# Interface_Load_Switching.net
KiCad netlist of a schematic drawn in Altium Designer
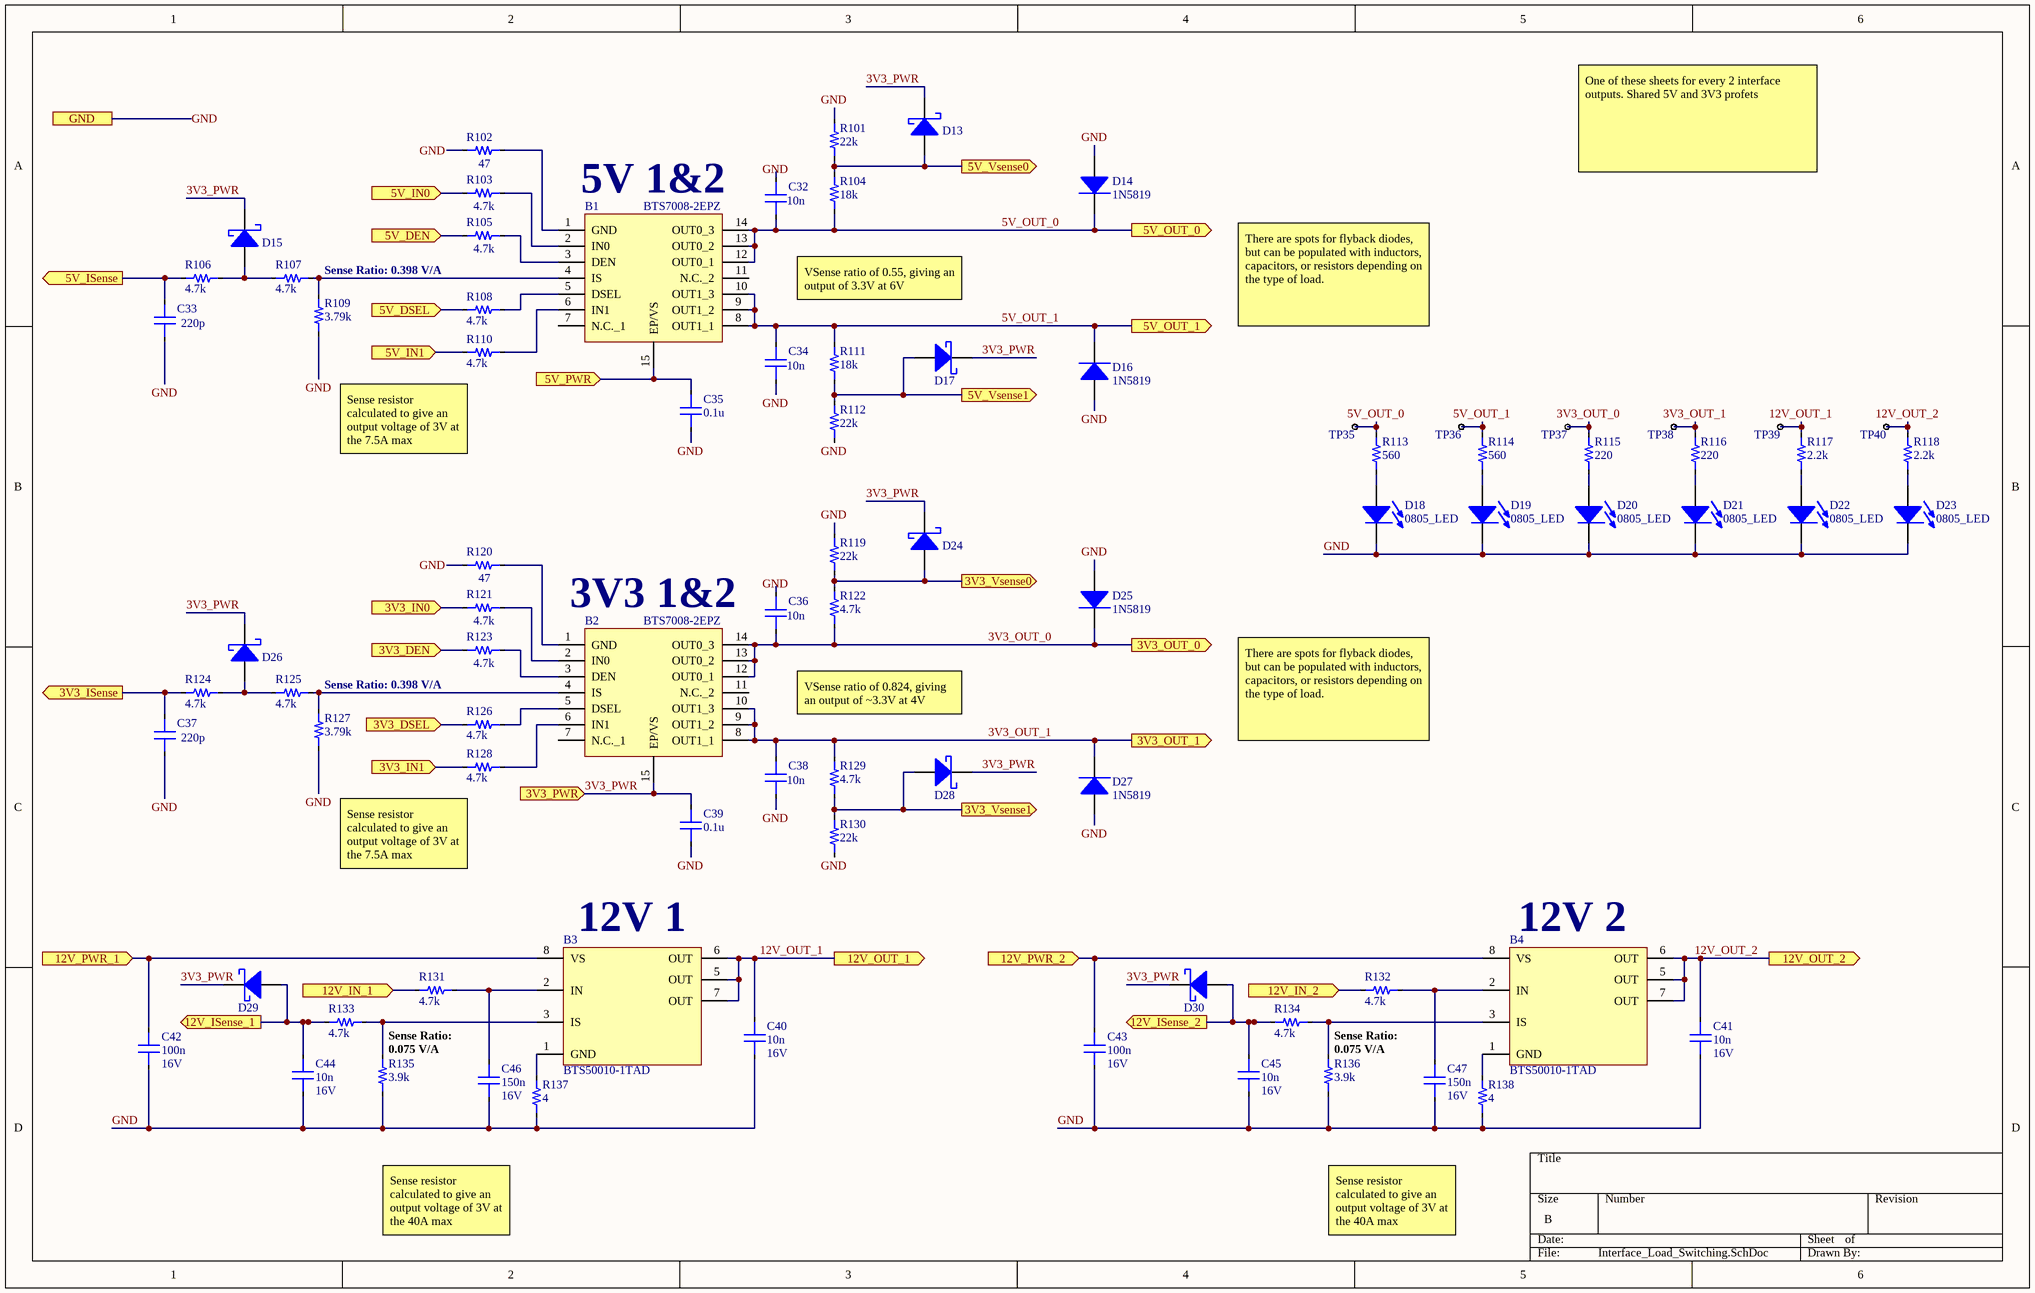
[diagram p0: Interface_Load_Switching.SchDoc]

(export (version "E")
  (design (tool "Eeschema 10.0.6"))
  (components
    (comp (ref "B1")
      (value "BTS7008-2EPZ")
      (footprint "SOP65P600X115-15N")
      (description "PROFET +2 12V Smart High-Side Power Switch")
      (libsource (lib "FETs") (part "BTS7008-2EPZ"))
    )
    (comp (ref "B2")
      (value "BTS7008-2EPZ")
      (footprint "SOP65P600X115-15N")
      (description "PROFET +2 12V Smart High-Side Power Switch")
      (libsource (lib "FETs") (part "BTS7008-2EPZ"))
    )
    (comp (ref "B3")
      (value "BTS50010-1TAD")
      (footprint "TO-263-7")
      (description "Power Switch/Driver 1:1 N-Channel 48A P/PG-TO-263-7-10")
      (libsource (lib "FETs") (part "BTS50010-1TAD"))
    )
    (comp (ref "B4")
      (value "BTS50010-1TAD")
      (footprint "TO-263-7")
      (description "Power Switch/Driver 1:1 N-Channel 48A P/PG-TO-263-7-10")
      (libsource (lib "FETs") (part "BTS50010-1TAD"))
    )
    (comp (ref "C32")
      (value "10n")
      (footprint "0603_CAP")
      (description "Protection of BTS7008-2EPZ output during ESD events and BCI")
      (fields (field (name "VOLTAGE") "16V") (field (name "Comment") "Capacitor"))
      (libsource (lib "Capacitors") (part "Capacitor"))
    )
    (comp (ref "C33")
      (value "220p")
      (footprint "0603_CAP")
      (description "Sense signal filtering")
      (fields (field (name "VOLTAGE") "16V") (field (name "Comment") "Capacitor"))
      (libsource (lib "Capacitors") (part "Capacitor"))
    )
    (comp (ref "C34")
      (value "10n")
      (footprint "0603_CAP")
      (description "Protection of BTS7008-2EPZ output during ESD events and BCI")
      (fields (field (name "VOLTAGE") "16V") (field (name "Comment") "Capacitor"))
      (libsource (lib "Capacitors") (part "Capacitor"))
    )
    (comp (ref "C35")
      (value "0.1u")
      (footprint "0603_CAP")
      (fields (field (name "Comment") "Capacitor"))
      (libsource (lib "Capacitors") (part "Capacitor"))
    )
    (comp (ref "C36")
      (value "10n")
      (footprint "0603_CAP")
      (description "Protection of BTS7008-2EPZ output during ESD events and BCI")
      (fields (field (name "VOLTAGE") "16V") (field (name "Comment") "Capacitor"))
      (libsource (lib "Capacitors") (part "Capacitor"))
    )
    (comp (ref "C37")
      (value "220p")
      (footprint "0603_CAP")
      (description "Sense signal filtering")
      (fields (field (name "VOLTAGE") "16V") (field (name "Comment") "Capacitor"))
      (libsource (lib "Capacitors") (part "Capacitor"))
    )
    (comp (ref "C38")
      (value "10n")
      (footprint "0603_CAP")
      (description "Protection of BTS7008-2EPZ output during ESD events and BCI")
      (fields (field (name "VOLTAGE") "16V") (field (name "Comment") "Capacitor"))
      (libsource (lib "Capacitors") (part "Capacitor"))
    )
    (comp (ref "C39")
      (value "0.1u")
      (footprint "0603_CAP")
      (fields (field (name "Comment") "Capacitor"))
      (libsource (lib "Capacitors") (part "Capacitor"))
    )
    (comp (ref "C40")
      (value "10n")
      (footprint "0603_CAP")
      (fields (field (name "VOLTAGE") "16V") (field (name "Comment") "Capacitor"))
      (libsource (lib "Capacitors") (part "Capacitor"))
    )
    (comp (ref "C41")
      (value "10n")
      (footprint "0603_CAP")
      (fields (field (name "VOLTAGE") "16V") (field (name "Comment") "Capacitor"))
      (libsource (lib "Capacitors") (part "Capacitor"))
    )
    (comp (ref "C42")
      (value "100n")
      (footprint "0603_CAP")
      (fields (field (name "VOLTAGE") "16V") (field (name "Comment") "Capacitor"))
      (libsource (lib "Capacitors") (part "Capacitor"))
    )
    (comp (ref "C43")
      (value "100n")
      (footprint "0603_CAP")
      (fields (field (name "VOLTAGE") "16V") (field (name "Comment") "Capacitor"))
      (libsource (lib "Capacitors") (part "Capacitor"))
    )
    (comp (ref "C44")
      (value "10n")
      (footprint "0603_CAP")
      (fields (field (name "VOLTAGE") "16V") (field (name "Comment") "Capacitor"))
      (libsource (lib "Capacitors") (part "Capacitor"))
    )
    (comp (ref "C45")
      (value "10n")
      (footprint "0603_CAP")
      (fields (field (name "VOLTAGE") "16V") (field (name "Comment") "Capacitor"))
      (libsource (lib "Capacitors") (part "Capacitor"))
    )
    (comp (ref "C46")
      (value "150n")
      (footprint "0603_CAP")
      (fields (field (name "VOLTAGE") "16V") (field (name "Comment") "Capacitor"))
      (libsource (lib "Capacitors") (part "Capacitor"))
    )
    (comp (ref "C47")
      (value "150n")
      (footprint "0603_CAP")
      (fields (field (name "VOLTAGE") "16V") (field (name "Comment") "Capacitor"))
      (libsource (lib "Capacitors") (part "Capacitor"))
    )
    (comp (ref "D13")
      (value "RBR2MM30BTFTR")
      (footprint "SOD-123F")
      (description "Diode Schottky 30 V 2A Surface Mount SOD-123F")
      (libsource (lib "Diodes") (part "RBR2MM30BTFTR"))
    )
    (comp (ref "D14")
      (value "1N5819")
      (footprint "SOD-123F")
      (description "Diode Super Barrier 40V 1A Surface Mount SOD-123F")
      (libsource (lib "Diodes") (part "1N5819"))
    )
    (comp (ref "D15")
      (value "RBR2MM30BTFTR")
      (footprint "SOD-123F")
      (description "Diode Schottky 30 V 2A Surface Mount SOD-123F")
      (libsource (lib "Diodes") (part "RBR2MM30BTFTR"))
    )
    (comp (ref "D16")
      (value "1N5819")
      (footprint "SOD-123F")
      (description "Diode Super Barrier 40V 1A Surface Mount SOD-123F")
      (libsource (lib "Diodes") (part "1N5819"))
    )
    (comp (ref "D17")
      (value "RBR2MM30BTFTR")
      (footprint "SOD-123F")
      (description "Diode Schottky 30 V 2A Surface Mount SOD-123F")
      (libsource (lib "Diodes") (part "RBR2MM30BTFTR"))
    )
    (comp (ref "D18")
      (value "0805_LED")
      (footprint "0805_LED")
      (description "Generic 0805 LED")
      (libsource (lib "Diodes") (part "0805_LED"))
    )
    (comp (ref "D19")
      (value "0805_LED")
      (footprint "0805_LED")
      (description "Generic 0805 LED")
      (libsource (lib "Diodes") (part "0805_LED"))
    )
    (comp (ref "D20")
      (value "0805_LED")
      (footprint "0805_LED")
      (description "Generic 0805 LED")
      (libsource (lib "Diodes") (part "0805_LED"))
    )
    (comp (ref "D21")
      (value "0805_LED")
      (footprint "0805_LED")
      (description "Generic 0805 LED")
      (libsource (lib "Diodes") (part "0805_LED"))
    )
    (comp (ref "D22")
      (value "0805_LED")
      (footprint "0805_LED")
      (description "Generic 0805 LED")
      (libsource (lib "Diodes") (part "0805_LED"))
    )
    (comp (ref "D23")
      (value "0805_LED")
      (footprint "0805_LED")
      (description "Generic 0805 LED")
      (libsource (lib "Diodes") (part "0805_LED"))
    )
    (comp (ref "D24")
      (value "RBR2MM30BTFTR")
      (footprint "SOD-123F")
      (description "Diode Schottky 30 V 2A Surface Mount SOD-123F")
      (libsource (lib "Diodes") (part "RBR2MM30BTFTR"))
    )
    (comp (ref "D25")
      (value "1N5819")
      (footprint "SOD-123F")
      (description "Diode Super Barrier 40V 1A Surface Mount SOD-123F")
      (libsource (lib "Diodes") (part "1N5819"))
    )
    (comp (ref "D26")
      (value "RBR2MM30BTFTR")
      (footprint "SOD-123F")
      (description "Diode Schottky 30 V 2A Surface Mount SOD-123F")
      (libsource (lib "Diodes") (part "RBR2MM30BTFTR"))
    )
    (comp (ref "D27")
      (value "1N5819")
      (footprint "SOD-123F")
      (description "Diode Super Barrier 40V 1A Surface Mount SOD-123F")
      (libsource (lib "Diodes") (part "1N5819"))
    )
    (comp (ref "D28")
      (value "RBR2MM30BTFTR")
      (footprint "SOD-123F")
      (description "Diode Schottky 30 V 2A Surface Mount SOD-123F")
      (libsource (lib "Diodes") (part "RBR2MM30BTFTR"))
    )
    (comp (ref "D29")
      (value "RBR2MM30BTFTR")
      (footprint "SOD-123F")
      (description "Diode Schottky 30 V 2A Surface Mount SOD-123F")
      (libsource (lib "Diodes") (part "RBR2MM30BTFTR"))
    )
    (comp (ref "D30")
      (value "RBR2MM30BTFTR")
      (footprint "SOD-123F")
      (description "Diode Schottky 30 V 2A Surface Mount SOD-123F")
      (libsource (lib "Diodes") (part "RBR2MM30BTFTR"))
    )
    (comp (ref "R101")
      (value "22k")
      (footprint "0603_RES")
      (fields (field (name "TOLERANCE") "1%") (field (name "Comment") "Resistor"))
      (libsource (lib "Resistors") (part "Resistor"))
    )
    (comp (ref "R102")
      (value "47")
      (footprint "0603_RES")
      (fields (field (name "Comment") "Resistor"))
      (libsource (lib "Resistors") (part "Resistor"))
    )
    (comp (ref "R103")
      (value "4.7k")
      (footprint "0603_RES")
      (fields (field (name "Comment") "R(IN)"))
      (libsource (lib "Resistors") (part "Resistor"))
    )
    (comp (ref "R104")
      (value "18k")
      (footprint "0603_RES")
      (fields (field (name "TOLERANCE") "1%") (field (name "Comment") "Resistor"))
      (libsource (lib "Resistors") (part "Resistor"))
    )
    (comp (ref "R105")
      (value "4.7k")
      (footprint "0603_RES")
      (fields (field (name "Comment") "Resistor"))
      (libsource (lib "Resistors") (part "Resistor"))
    )
    (comp (ref "R106")
      (value "4.7k")
      (footprint "0603_RES")
      (fields (field (name "Comment") "Resistor"))
      (libsource (lib "Resistors") (part "Resistor"))
    )
    (comp (ref "R107")
      (value "4.7k")
      (footprint "0603_RES")
      (fields (field (name "Comment") "Resistor"))
      (libsource (lib "Resistors") (part "Resistor"))
    )
    (comp (ref "R108")
      (value "4.7k")
      (footprint "0603_RES")
      (fields (field (name "Comment") "Resistor"))
      (libsource (lib "Resistors") (part "Resistor"))
    )
    (comp (ref "R109")
      (value "3.79k")
      (footprint "0603_RES")
      (description "SENSE resistor")
      (fields (field (name "TOLERANCE") "1%") (field (name "Comment") "Resistor"))
      (libsource (lib "Resistors") (part "Resistor"))
    )
    (comp (ref "R110")
      (value "4.7k")
      (footprint "0603_RES")
      (fields (field (name "Comment") "Resistor"))
      (libsource (lib "Resistors") (part "Resistor"))
    )
    (comp (ref "R111")
      (value "18k")
      (footprint "0603_RES")
      (fields (field (name "TOLERANCE") "1%") (field (name "Comment") "Resistor"))
      (libsource (lib "Resistors") (part "Resistor"))
    )
    (comp (ref "R112")
      (value "22k")
      (footprint "0603_RES")
      (fields (field (name "TOLERANCE") "1%") (field (name "Comment") "Resistor"))
      (libsource (lib "Resistors") (part "Resistor"))
    )
    (comp (ref "R113")
      (value "560")
      (footprint "0603_RES")
      (fields (field (name "Comment") "Resistor"))
      (libsource (lib "Resistors") (part "Resistor"))
    )
    (comp (ref "R114")
      (value "560")
      (footprint "0603_RES")
      (fields (field (name "Comment") "Resistor"))
      (libsource (lib "Resistors") (part "Resistor"))
    )
    (comp (ref "R115")
      (value "220")
      (footprint "0603_RES")
      (fields (field (name "Comment") "Resistor"))
      (libsource (lib "Resistors") (part "Resistor"))
    )
    (comp (ref "R116")
      (value "220")
      (footprint "0603_RES")
      (fields (field (name "Comment") "Resistor"))
      (libsource (lib "Resistors") (part "Resistor"))
    )
    (comp (ref "R117")
      (value "2.2k")
      (footprint "0603_RES")
      (fields (field (name "Comment") "Resistor"))
      (libsource (lib "Resistors") (part "Resistor"))
    )
    (comp (ref "R118")
      (value "2.2k")
      (footprint "0603_RES")
      (fields (field (name "Comment") "Resistor"))
      (libsource (lib "Resistors") (part "Resistor"))
    )
    (comp (ref "R119")
      (value "22k")
      (footprint "0603_RES")
      (fields (field (name "TOLERANCE") "1%") (field (name "Comment") "Resistor"))
      (libsource (lib "Resistors") (part "Resistor"))
    )
    (comp (ref "R120")
      (value "47")
      (footprint "0603_RES")
      (fields (field (name "Comment") "Resistor"))
      (libsource (lib "Resistors") (part "Resistor"))
    )
    (comp (ref "R121")
      (value "4.7k")
      (footprint "0603_RES")
      (fields (field (name "Comment") "R(IN)"))
      (libsource (lib "Resistors") (part "Resistor"))
    )
    (comp (ref "R122")
      (value "4.7k")
      (footprint "0603_RES")
      (fields (field (name "TOLERANCE") "1%") (field (name "Comment") "Resistor"))
      (libsource (lib "Resistors") (part "Resistor"))
    )
    (comp (ref "R123")
      (value "4.7k")
      (footprint "0603_RES")
      (fields (field (name "Comment") "Resistor"))
      (libsource (lib "Resistors") (part "Resistor"))
    )
    (comp (ref "R124")
      (value "4.7k")
      (footprint "0603_RES")
      (fields (field (name "Comment") "Resistor"))
      (libsource (lib "Resistors") (part "Resistor"))
    )
    (comp (ref "R125")
      (value "4.7k")
      (footprint "0603_RES")
      (fields (field (name "Comment") "Resistor"))
      (libsource (lib "Resistors") (part "Resistor"))
    )
    (comp (ref "R126")
      (value "4.7k")
      (footprint "0603_RES")
      (fields (field (name "Comment") "Resistor"))
      (libsource (lib "Resistors") (part "Resistor"))
    )
    (comp (ref "R127")
      (value "3.79k")
      (footprint "0603_RES")
      (description "SENSE resistor")
      (fields (field (name "TOLERANCE") "1%") (field (name "Comment") "Resistor"))
      (libsource (lib "Resistors") (part "Resistor"))
    )
    (comp (ref "R128")
      (value "4.7k")
      (footprint "0603_RES")
      (fields (field (name "Comment") "Resistor"))
      (libsource (lib "Resistors") (part "Resistor"))
    )
    (comp (ref "R129")
      (value "4.7k")
      (footprint "0603_RES")
      (fields (field (name "TOLERANCE") "1%") (field (name "Comment") "Resistor"))
      (libsource (lib "Resistors") (part "Resistor"))
    )
    (comp (ref "R130")
      (value "22k")
      (footprint "0603_RES")
      (fields (field (name "TOLERANCE") "1%") (field (name "Comment") "Resistor"))
      (libsource (lib "Resistors") (part "Resistor"))
    )
    (comp (ref "R131")
      (value "4.7k")
      (footprint "0603_RES")
      (fields (field (name "Comment") "Resistor"))
      (libsource (lib "Resistors") (part "Resistor"))
    )
    (comp (ref "R132")
      (value "4.7k")
      (footprint "0603_RES")
      (fields (field (name "Comment") "Resistor"))
      (libsource (lib "Resistors") (part "Resistor"))
    )
    (comp (ref "R133")
      (value "4.7k")
      (footprint "0603_RES")
      (fields (field (name "Comment") "Resistor"))
      (libsource (lib "Resistors") (part "Resistor"))
    )
    (comp (ref "R134")
      (value "4.7k")
      (footprint "0603_RES")
      (fields (field (name "Comment") "Resistor"))
      (libsource (lib "Resistors") (part "Resistor"))
    )
    (comp (ref "R135")
      (value "3.9k")
      (footprint "0603_RES")
      (fields (field (name "TOLERANCE") "1%") (field (name "Comment") "Resistor"))
      (libsource (lib "Resistors") (part "Resistor"))
    )
    (comp (ref "R136")
      (value "3.9k")
      (footprint "0603_RES")
      (fields (field (name "TOLERANCE") "1%") (field (name "Comment") "Resistor"))
      (libsource (lib "Resistors") (part "Resistor"))
    )
    (comp (ref "R137")
      (value "4")
      (footprint "0805_RES")
      (fields (field (name "Comment") "Resistor"))
      (libsource (lib "Resistors") (part "Resistor"))
    )
    (comp (ref "R138")
      (value "4")
      (footprint "0805_RES")
      (fields (field (name "Comment") "Resistor"))
      (libsource (lib "Resistors") (part "Resistor"))
    )
    (comp (ref "TP35")
      (value "1mm Testpoint")
      (footprint "1mm_testpoint")
      (description "1mm test point")
      (libsource (lib "Connectors") (part "1mm Testpoint"))
    )
    (comp (ref "TP36")
      (value "1mm Testpoint")
      (footprint "1mm_testpoint")
      (description "1mm test point")
      (libsource (lib "Connectors") (part "1mm Testpoint"))
    )
    (comp (ref "TP37")
      (value "1mm Testpoint")
      (footprint "1mm_testpoint")
      (description "1mm test point")
      (libsource (lib "Connectors") (part "1mm Testpoint"))
    )
    (comp (ref "TP38")
      (value "1mm Testpoint")
      (footprint "1mm_testpoint")
      (description "1mm test point")
      (libsource (lib "Connectors") (part "1mm Testpoint"))
    )
    (comp (ref "TP39")
      (value "1mm Testpoint")
      (footprint "1mm_testpoint")
      (description "1mm test point")
      (libsource (lib "Connectors") (part "1mm Testpoint"))
    )
    (comp (ref "TP40")
      (value "1mm Testpoint")
      (footprint "1mm_testpoint")
      (description "1mm test point")
      (libsource (lib "Connectors") (part "1mm Testpoint"))
    )
  )
  (nets
    (net (code "1") (name "/3V3_DEN") (class "Default")
      (node (ref "R123") (pin "2") (pinfunction "2_2") (pintype "passive"))
    )
    (net (code "2") (name "/3V3_DSEL") (class "Default")
      (node (ref "R126") (pin "1") (pinfunction "1_1") (pintype "passive"))
    )
    (net (code "3") (name "/3V3_IN0") (class "Default")
      (node (ref "R121") (pin "2") (pinfunction "2_2") (pintype "passive"))
    )
    (net (code "4") (name "/3V3_IN1") (class "Default")
      (node (ref "R128") (pin "2") (pinfunction "2_2") (pintype "passive"))
    )
    (net (code "5") (name "/3V3_ISense") (class "Default")
      (node (ref "C37") (pin "2") (pinfunction "2_2") (pintype "passive"))
      (node (ref "R124") (pin "1") (pinfunction "1_1") (pintype "passive"))
    )
    (net (code "6") (name "/3V3_OUT_0") (class "Default")
      (node (ref "B2") (pin "12") (pinfunction "OUT0_1_12") (pintype "passive"))
      (node (ref "B2") (pin "13") (pinfunction "OUT0_2_13") (pintype "passive"))
      (node (ref "B2") (pin "14") (pinfunction "OUT0_3_14") (pintype "passive"))
      (node (ref "C36") (pin "1") (pinfunction "1_1") (pintype "passive"))
      (node (ref "D25") (pin "1") (pintype "passive"))
      (node (ref "R115") (pin "2") (pinfunction "2_2") (pintype "passive"))
      (node (ref "R122") (pin "1") (pinfunction "1_1") (pintype "passive"))
      (node (ref "TP37") (pin "1") (pintype "passive"))
    )
    (net (code "7") (name "/3V3_OUT_1") (class "Default")
      (node (ref "B2") (pin "10") (pinfunction "OUT1_3_10") (pintype "passive"))
      (node (ref "B2") (pin "8") (pinfunction "OUT1_1_8") (pintype "passive"))
      (node (ref "B2") (pin "9") (pinfunction "OUT1_2_9") (pintype "passive"))
      (node (ref "C38") (pin "2") (pinfunction "2_2") (pintype "passive"))
      (node (ref "D27") (pin "1") (pintype "passive"))
      (node (ref "R116") (pin "2") (pinfunction "2_2") (pintype "passive"))
      (node (ref "R129") (pin "1") (pinfunction "1_1") (pintype "passive"))
      (node (ref "TP38") (pin "1") (pintype "passive"))
    )
    (net (code "8") (name "/3V3_PWR") (class "Default")
      (node (ref "B2") (pin "15") (pinfunction "EP/VS_15") (pintype "passive"))
      (node (ref "C39") (pin "2") (pinfunction "2_2") (pintype "passive"))
      (node (ref "D13") (pin "1") (pinfunction "K_1") (pintype "passive"))
      (node (ref "D15") (pin "1") (pinfunction "K_1") (pintype "passive"))
      (node (ref "D17") (pin "1") (pinfunction "K_1") (pintype "passive"))
      (node (ref "D24") (pin "1") (pinfunction "K_1") (pintype "passive"))
      (node (ref "D26") (pin "1") (pinfunction "K_1") (pintype "passive"))
      (node (ref "D28") (pin "1") (pinfunction "K_1") (pintype "passive"))
      (node (ref "D29") (pin "1") (pinfunction "K_1") (pintype "passive"))
      (node (ref "D30") (pin "1") (pinfunction "K_1") (pintype "passive"))
    )
    (net (code "9") (name "/3V3_Vsense0") (class "Default")
      (node (ref "D24") (pin "2") (pinfunction "A_2") (pintype "passive"))
      (node (ref "R119") (pin "1") (pinfunction "1_1") (pintype "passive"))
      (node (ref "R122") (pin "2") (pinfunction "2_2") (pintype "passive"))
    )
    (net (code "10") (name "/3V3_Vsense1") (class "Default")
      (node (ref "D28") (pin "2") (pinfunction "A_2") (pintype "passive"))
      (node (ref "R129") (pin "2") (pinfunction "2_2") (pintype "passive"))
      (node (ref "R130") (pin "1") (pinfunction "1_1") (pintype "passive"))
    )
    (net (code "11") (name "/5V_DEN") (class "Default")
      (node (ref "R105") (pin "2") (pinfunction "2_2") (pintype "passive"))
    )
    (net (code "12") (name "/5V_DSEL") (class "Default")
      (node (ref "R108") (pin "1") (pinfunction "1_1") (pintype "passive"))
    )
    (net (code "13") (name "/5V_IN0") (class "Default")
      (node (ref "R103") (pin "2") (pinfunction "2_2") (pintype "passive"))
    )
    (net (code "14") (name "/5V_IN1") (class "Default")
      (node (ref "R110") (pin "2") (pinfunction "2_2") (pintype "passive"))
    )
    (net (code "15") (name "/5V_ISense") (class "Default")
      (node (ref "C33") (pin "2") (pinfunction "2_2") (pintype "passive"))
      (node (ref "R106") (pin "1") (pinfunction "1_1") (pintype "passive"))
    )
    (net (code "16") (name "/5V_OUT_0") (class "Default")
      (node (ref "B1") (pin "12") (pinfunction "OUT0_1_12") (pintype "passive"))
      (node (ref "B1") (pin "13") (pinfunction "OUT0_2_13") (pintype "passive"))
      (node (ref "B1") (pin "14") (pinfunction "OUT0_3_14") (pintype "passive"))
      (node (ref "C32") (pin "1") (pinfunction "1_1") (pintype "passive"))
      (node (ref "D14") (pin "1") (pintype "passive"))
      (node (ref "R104") (pin "1") (pinfunction "1_1") (pintype "passive"))
      (node (ref "R113") (pin "2") (pinfunction "2_2") (pintype "passive"))
      (node (ref "TP35") (pin "1") (pintype "passive"))
    )
    (net (code "17") (name "/5V_OUT_1") (class "Default")
      (node (ref "B1") (pin "10") (pinfunction "OUT1_3_10") (pintype "passive"))
      (node (ref "B1") (pin "8") (pinfunction "OUT1_1_8") (pintype "passive"))
      (node (ref "B1") (pin "9") (pinfunction "OUT1_2_9") (pintype "passive"))
      (node (ref "C34") (pin "2") (pinfunction "2_2") (pintype "passive"))
      (node (ref "D16") (pin "1") (pintype "passive"))
      (node (ref "R111") (pin "1") (pinfunction "1_1") (pintype "passive"))
      (node (ref "R114") (pin "2") (pinfunction "2_2") (pintype "passive"))
      (node (ref "TP36") (pin "1") (pintype "passive"))
    )
    (net (code "18") (name "/5V_PWR") (class "Default")
      (node (ref "B1") (pin "15") (pinfunction "EP/VS_15") (pintype "passive"))
      (node (ref "C35") (pin "2") (pinfunction "2_2") (pintype "passive"))
    )
    (net (code "19") (name "/5V_Vsense0") (class "Default")
      (node (ref "D13") (pin "2") (pinfunction "A_2") (pintype "passive"))
      (node (ref "R101") (pin "1") (pinfunction "1_1") (pintype "passive"))
      (node (ref "R104") (pin "2") (pinfunction "2_2") (pintype "passive"))
    )
    (net (code "20") (name "/5V_Vsense1") (class "Default")
      (node (ref "D17") (pin "2") (pinfunction "A_2") (pintype "passive"))
      (node (ref "R111") (pin "2") (pinfunction "2_2") (pintype "passive"))
      (node (ref "R112") (pin "1") (pinfunction "1_1") (pintype "passive"))
    )
    (net (code "21") (name "/12V_IN_1") (class "Default")
      (node (ref "R131") (pin "1") (pinfunction "1_1") (pintype "passive"))
    )
    (net (code "22") (name "/12V_IN_2") (class "Default")
      (node (ref "R132") (pin "1") (pinfunction "1_1") (pintype "passive"))
    )
    (net (code "23") (name "/12V_ISense_1") (class "Default")
      (node (ref "C44") (pin "2") (pinfunction "2_2") (pintype "passive"))
      (node (ref "D29") (pin "2") (pinfunction "A_2") (pintype "passive"))
      (node (ref "R133") (pin "1") (pinfunction "1_1") (pintype "passive"))
    )
    (net (code "24") (name "/12V_ISense_2") (class "Default")
      (node (ref "C45") (pin "2") (pinfunction "2_2") (pintype "passive"))
      (node (ref "D30") (pin "2") (pinfunction "A_2") (pintype "passive"))
      (node (ref "R134") (pin "1") (pinfunction "1_1") (pintype "passive"))
    )
    (net (code "25") (name "/12V_OUT_1") (class "Default")
      (node (ref "B3") (pin "5") (pinfunction "OUT_5") (pintype "passive"))
      (node (ref "B3") (pin "6") (pinfunction "OUT_6") (pintype "passive"))
      (node (ref "B3") (pin "7") (pinfunction "OUT_7") (pintype "passive"))
      (node (ref "C40") (pin "2") (pinfunction "2_2") (pintype "passive"))
      (node (ref "R117") (pin "2") (pinfunction "2_2") (pintype "passive"))
      (node (ref "TP39") (pin "1") (pintype "passive"))
    )
    (net (code "26") (name "/12V_OUT_2") (class "Default")
      (node (ref "B4") (pin "5") (pinfunction "OUT_5") (pintype "passive"))
      (node (ref "B4") (pin "6") (pinfunction "OUT_6") (pintype "passive"))
      (node (ref "B4") (pin "7") (pinfunction "OUT_7") (pintype "passive"))
      (node (ref "C41") (pin "2") (pinfunction "2_2") (pintype "passive"))
      (node (ref "R118") (pin "2") (pinfunction "2_2") (pintype "passive"))
      (node (ref "TP40") (pin "1") (pintype "passive"))
    )
    (net (code "27") (name "/12V_PWR_1") (class "Default")
      (node (ref "B3") (pin "8") (pinfunction "VS_8") (pintype "passive"))
      (node (ref "C42") (pin "2") (pinfunction "2_2") (pintype "passive"))
    )
    (net (code "28") (name "/12V_PWR_2") (class "Default")
      (node (ref "B4") (pin "8") (pinfunction "VS_8") (pintype "passive"))
      (node (ref "C43") (pin "2") (pinfunction "2_2") (pintype "passive"))
    )
    (net (code "29") (name "/GND") (class "Default")
      (node (ref "C32") (pin "2") (pinfunction "2_2") (pintype "passive"))
      (node (ref "C33") (pin "1") (pinfunction "1_1") (pintype "passive"))
      (node (ref "C34") (pin "1") (pinfunction "1_1") (pintype "passive"))
      (node (ref "C35") (pin "1") (pinfunction "1_1") (pintype "passive"))
      (node (ref "C36") (pin "2") (pinfunction "2_2") (pintype "passive"))
      (node (ref "C37") (pin "1") (pinfunction "1_1") (pintype "passive"))
      (node (ref "C38") (pin "1") (pinfunction "1_1") (pintype "passive"))
      (node (ref "C39") (pin "1") (pinfunction "1_1") (pintype "passive"))
      (node (ref "C40") (pin "1") (pinfunction "1_1") (pintype "passive"))
      (node (ref "C41") (pin "1") (pinfunction "1_1") (pintype "passive"))
      (node (ref "C42") (pin "1") (pinfunction "1_1") (pintype "passive"))
      (node (ref "C43") (pin "1") (pinfunction "1_1") (pintype "passive"))
      (node (ref "C44") (pin "1") (pinfunction "1_1") (pintype "passive"))
      (node (ref "C45") (pin "1") (pinfunction "1_1") (pintype "passive"))
      (node (ref "C46") (pin "1") (pinfunction "1_1") (pintype "passive"))
      (node (ref "C47") (pin "1") (pinfunction "1_1") (pintype "passive"))
      (node (ref "D14") (pin "2") (pintype "passive"))
      (node (ref "D16") (pin "2") (pintype "passive"))
      (node (ref "D18") (pin "2") (pinfunction "K_2") (pintype "passive"))
      (node (ref "D19") (pin "2") (pinfunction "K_2") (pintype "passive"))
      (node (ref "D20") (pin "2") (pinfunction "K_2") (pintype "passive"))
      (node (ref "D21") (pin "2") (pinfunction "K_2") (pintype "passive"))
      (node (ref "D22") (pin "2") (pinfunction "K_2") (pintype "passive"))
      (node (ref "D23") (pin "2") (pinfunction "K_2") (pintype "passive"))
      (node (ref "D25") (pin "2") (pintype "passive"))
      (node (ref "D27") (pin "2") (pintype "passive"))
      (node (ref "R101") (pin "2") (pinfunction "2_2") (pintype "passive"))
      (node (ref "R102") (pin "2") (pinfunction "2_2") (pintype "passive"))
      (node (ref "R109") (pin "1") (pinfunction "1_1") (pintype "passive"))
      (node (ref "R112") (pin "2") (pinfunction "2_2") (pintype "passive"))
      (node (ref "R119") (pin "2") (pinfunction "2_2") (pintype "passive"))
      (node (ref "R120") (pin "2") (pinfunction "2_2") (pintype "passive"))
      (node (ref "R127") (pin "1") (pinfunction "1_1") (pintype "passive"))
      (node (ref "R130") (pin "2") (pinfunction "2_2") (pintype "passive"))
      (node (ref "R135") (pin "1") (pinfunction "1_1") (pintype "passive"))
      (node (ref "R136") (pin "1") (pinfunction "1_1") (pintype "passive"))
      (node (ref "R137") (pin "1") (pinfunction "1_1") (pintype "passive"))
      (node (ref "R138") (pin "1") (pinfunction "1_1") (pintype "passive"))
    )
    (net (code "30") (name "Net-(B1-DEN)") (class "Default")
      (node (ref "B1") (pin "3") (pinfunction "DEN_3") (pintype "passive"))
      (node (ref "R105") (pin "1") (pinfunction "1_1") (pintype "passive"))
    )
    (net (code "31") (name "Net-(B1-DSEL)") (class "Default")
      (node (ref "B1") (pin "5") (pinfunction "DSEL_5") (pintype "passive"))
      (node (ref "R108") (pin "2") (pinfunction "2_2") (pintype "passive"))
    )
    (net (code "32") (name "Net-(B1-GND)") (class "Default")
      (node (ref "B1") (pin "1") (pinfunction "GND_1") (pintype "passive"))
      (node (ref "R102") (pin "1") (pinfunction "1_1") (pintype "passive"))
    )
    (net (code "33") (name "Net-(B1-IN0)") (class "Default")
      (node (ref "B1") (pin "2") (pinfunction "IN0_2") (pintype "passive"))
      (node (ref "R103") (pin "1") (pinfunction "1_1") (pintype "passive"))
    )
    (net (code "34") (name "Net-(B1-IN1)") (class "Default")
      (node (ref "B1") (pin "6") (pinfunction "IN1_6") (pintype "passive"))
      (node (ref "R110") (pin "1") (pinfunction "1_1") (pintype "passive"))
    )
    (net (code "35") (name "Net-(B1-IS)") (class "Default")
      (node (ref "B1") (pin "4") (pinfunction "IS_4") (pintype "passive"))
      (node (ref "R107") (pin "2") (pinfunction "2_2") (pintype "passive"))
      (node (ref "R109") (pin "2") (pinfunction "2_2") (pintype "passive"))
    )
    (net (code "36") (name "Net-(B2-DEN)") (class "Default")
      (node (ref "B2") (pin "3") (pinfunction "DEN_3") (pintype "passive"))
      (node (ref "R123") (pin "1") (pinfunction "1_1") (pintype "passive"))
    )
    (net (code "37") (name "Net-(B2-DSEL)") (class "Default")
      (node (ref "B2") (pin "5") (pinfunction "DSEL_5") (pintype "passive"))
      (node (ref "R126") (pin "2") (pinfunction "2_2") (pintype "passive"))
    )
    (net (code "38") (name "Net-(B2-GND)") (class "Default")
      (node (ref "B2") (pin "1") (pinfunction "GND_1") (pintype "passive"))
      (node (ref "R120") (pin "1") (pinfunction "1_1") (pintype "passive"))
    )
    (net (code "39") (name "Net-(B2-IN0)") (class "Default")
      (node (ref "B2") (pin "2") (pinfunction "IN0_2") (pintype "passive"))
      (node (ref "R121") (pin "1") (pinfunction "1_1") (pintype "passive"))
    )
    (net (code "40") (name "Net-(B2-IN1)") (class "Default")
      (node (ref "B2") (pin "6") (pinfunction "IN1_6") (pintype "passive"))
      (node (ref "R128") (pin "1") (pinfunction "1_1") (pintype "passive"))
    )
    (net (code "41") (name "Net-(B2-IS)") (class "Default")
      (node (ref "B2") (pin "4") (pinfunction "IS_4") (pintype "passive"))
      (node (ref "R125") (pin "2") (pinfunction "2_2") (pintype "passive"))
      (node (ref "R127") (pin "2") (pinfunction "2_2") (pintype "passive"))
    )
    (net (code "42") (name "Net-(B3-GND)") (class "Default")
      (node (ref "B3") (pin "1") (pinfunction "GND_1") (pintype "passive"))
      (node (ref "R137") (pin "2") (pinfunction "2_2") (pintype "passive"))
    )
    (net (code "43") (name "Net-(B3-IN)") (class "Default")
      (node (ref "B3") (pin "2") (pinfunction "IN_2") (pintype "passive"))
      (node (ref "C46") (pin "2") (pinfunction "2_2") (pintype "passive"))
      (node (ref "R131") (pin "2") (pinfunction "2_2") (pintype "passive"))
    )
    (net (code "44") (name "Net-(B3-IS)") (class "Default")
      (node (ref "B3") (pin "3") (pinfunction "IS_3") (pintype "passive"))
      (node (ref "R133") (pin "2") (pinfunction "2_2") (pintype "passive"))
      (node (ref "R135") (pin "2") (pinfunction "2_2") (pintype "passive"))
    )
    (net (code "45") (name "Net-(B4-GND)") (class "Default")
      (node (ref "B4") (pin "1") (pinfunction "GND_1") (pintype "passive"))
      (node (ref "R138") (pin "2") (pinfunction "2_2") (pintype "passive"))
    )
    (net (code "46") (name "Net-(B4-IN)") (class "Default")
      (node (ref "B4") (pin "2") (pinfunction "IN_2") (pintype "passive"))
      (node (ref "C47") (pin "2") (pinfunction "2_2") (pintype "passive"))
      (node (ref "R132") (pin "2") (pinfunction "2_2") (pintype "passive"))
    )
    (net (code "47") (name "Net-(B4-IS)") (class "Default")
      (node (ref "B4") (pin "3") (pinfunction "IS_3") (pintype "passive"))
      (node (ref "R134") (pin "2") (pinfunction "2_2") (pintype "passive"))
      (node (ref "R136") (pin "2") (pinfunction "2_2") (pintype "passive"))
    )
    (net (code "48") (name "Net-(D15-A)") (class "Default")
      (node (ref "D15") (pin "2") (pinfunction "A_2") (pintype "passive"))
      (node (ref "R106") (pin "2") (pinfunction "2_2") (pintype "passive"))
      (node (ref "R107") (pin "1") (pinfunction "1_1") (pintype "passive"))
    )
    (net (code "49") (name "Net-(D18-A)") (class "Default")
      (node (ref "D18") (pin "1") (pinfunction "A_1") (pintype "passive"))
      (node (ref "R113") (pin "1") (pinfunction "1_1") (pintype "passive"))
    )
    (net (code "50") (name "Net-(D19-A)") (class "Default")
      (node (ref "D19") (pin "1") (pinfunction "A_1") (pintype "passive"))
      (node (ref "R114") (pin "1") (pinfunction "1_1") (pintype "passive"))
    )
    (net (code "51") (name "Net-(D20-A)") (class "Default")
      (node (ref "D20") (pin "1") (pinfunction "A_1") (pintype "passive"))
      (node (ref "R115") (pin "1") (pinfunction "1_1") (pintype "passive"))
    )
    (net (code "52") (name "Net-(D21-A)") (class "Default")
      (node (ref "D21") (pin "1") (pinfunction "A_1") (pintype "passive"))
      (node (ref "R116") (pin "1") (pinfunction "1_1") (pintype "passive"))
    )
    (net (code "53") (name "Net-(D22-A)") (class "Default")
      (node (ref "D22") (pin "1") (pinfunction "A_1") (pintype "passive"))
      (node (ref "R117") (pin "1") (pinfunction "1_1") (pintype "passive"))
    )
    (net (code "54") (name "Net-(D23-A)") (class "Default")
      (node (ref "D23") (pin "1") (pinfunction "A_1") (pintype "passive"))
      (node (ref "R118") (pin "1") (pinfunction "1_1") (pintype "passive"))
    )
    (net (code "55") (name "Net-(D26-A)") (class "Default")
      (node (ref "D26") (pin "2") (pinfunction "A_2") (pintype "passive"))
      (node (ref "R124") (pin "2") (pinfunction "2_2") (pintype "passive"))
      (node (ref "R125") (pin "1") (pinfunction "1_1") (pintype "passive"))
    )
    (net (code "56") (name "unconnected-(B1-N.C._1-Pad7)") (class "Default")
      (node (ref "B1") (pin "7") (pinfunction "N.C._1_7") (pintype "passive"))
    )
    (net (code "57") (name "unconnected-(B1-N.C._2-Pad11)") (class "Default")
      (node (ref "B1") (pin "11") (pinfunction "N.C._2_11") (pintype "passive"))
    )
    (net (code "58") (name "unconnected-(B2-N.C._1-Pad7)") (class "Default")
      (node (ref "B2") (pin "7") (pinfunction "N.C._1_7") (pintype "passive"))
    )
    (net (code "59") (name "unconnected-(B2-N.C._2-Pad11)") (class "Default")
      (node (ref "B2") (pin "11") (pinfunction "N.C._2_11") (pintype "passive"))
    )
  )
)
